# PROC091F_HD_CONN_PWR_SW.net
KiCad netlist of a schematic drawn in Altium Designer
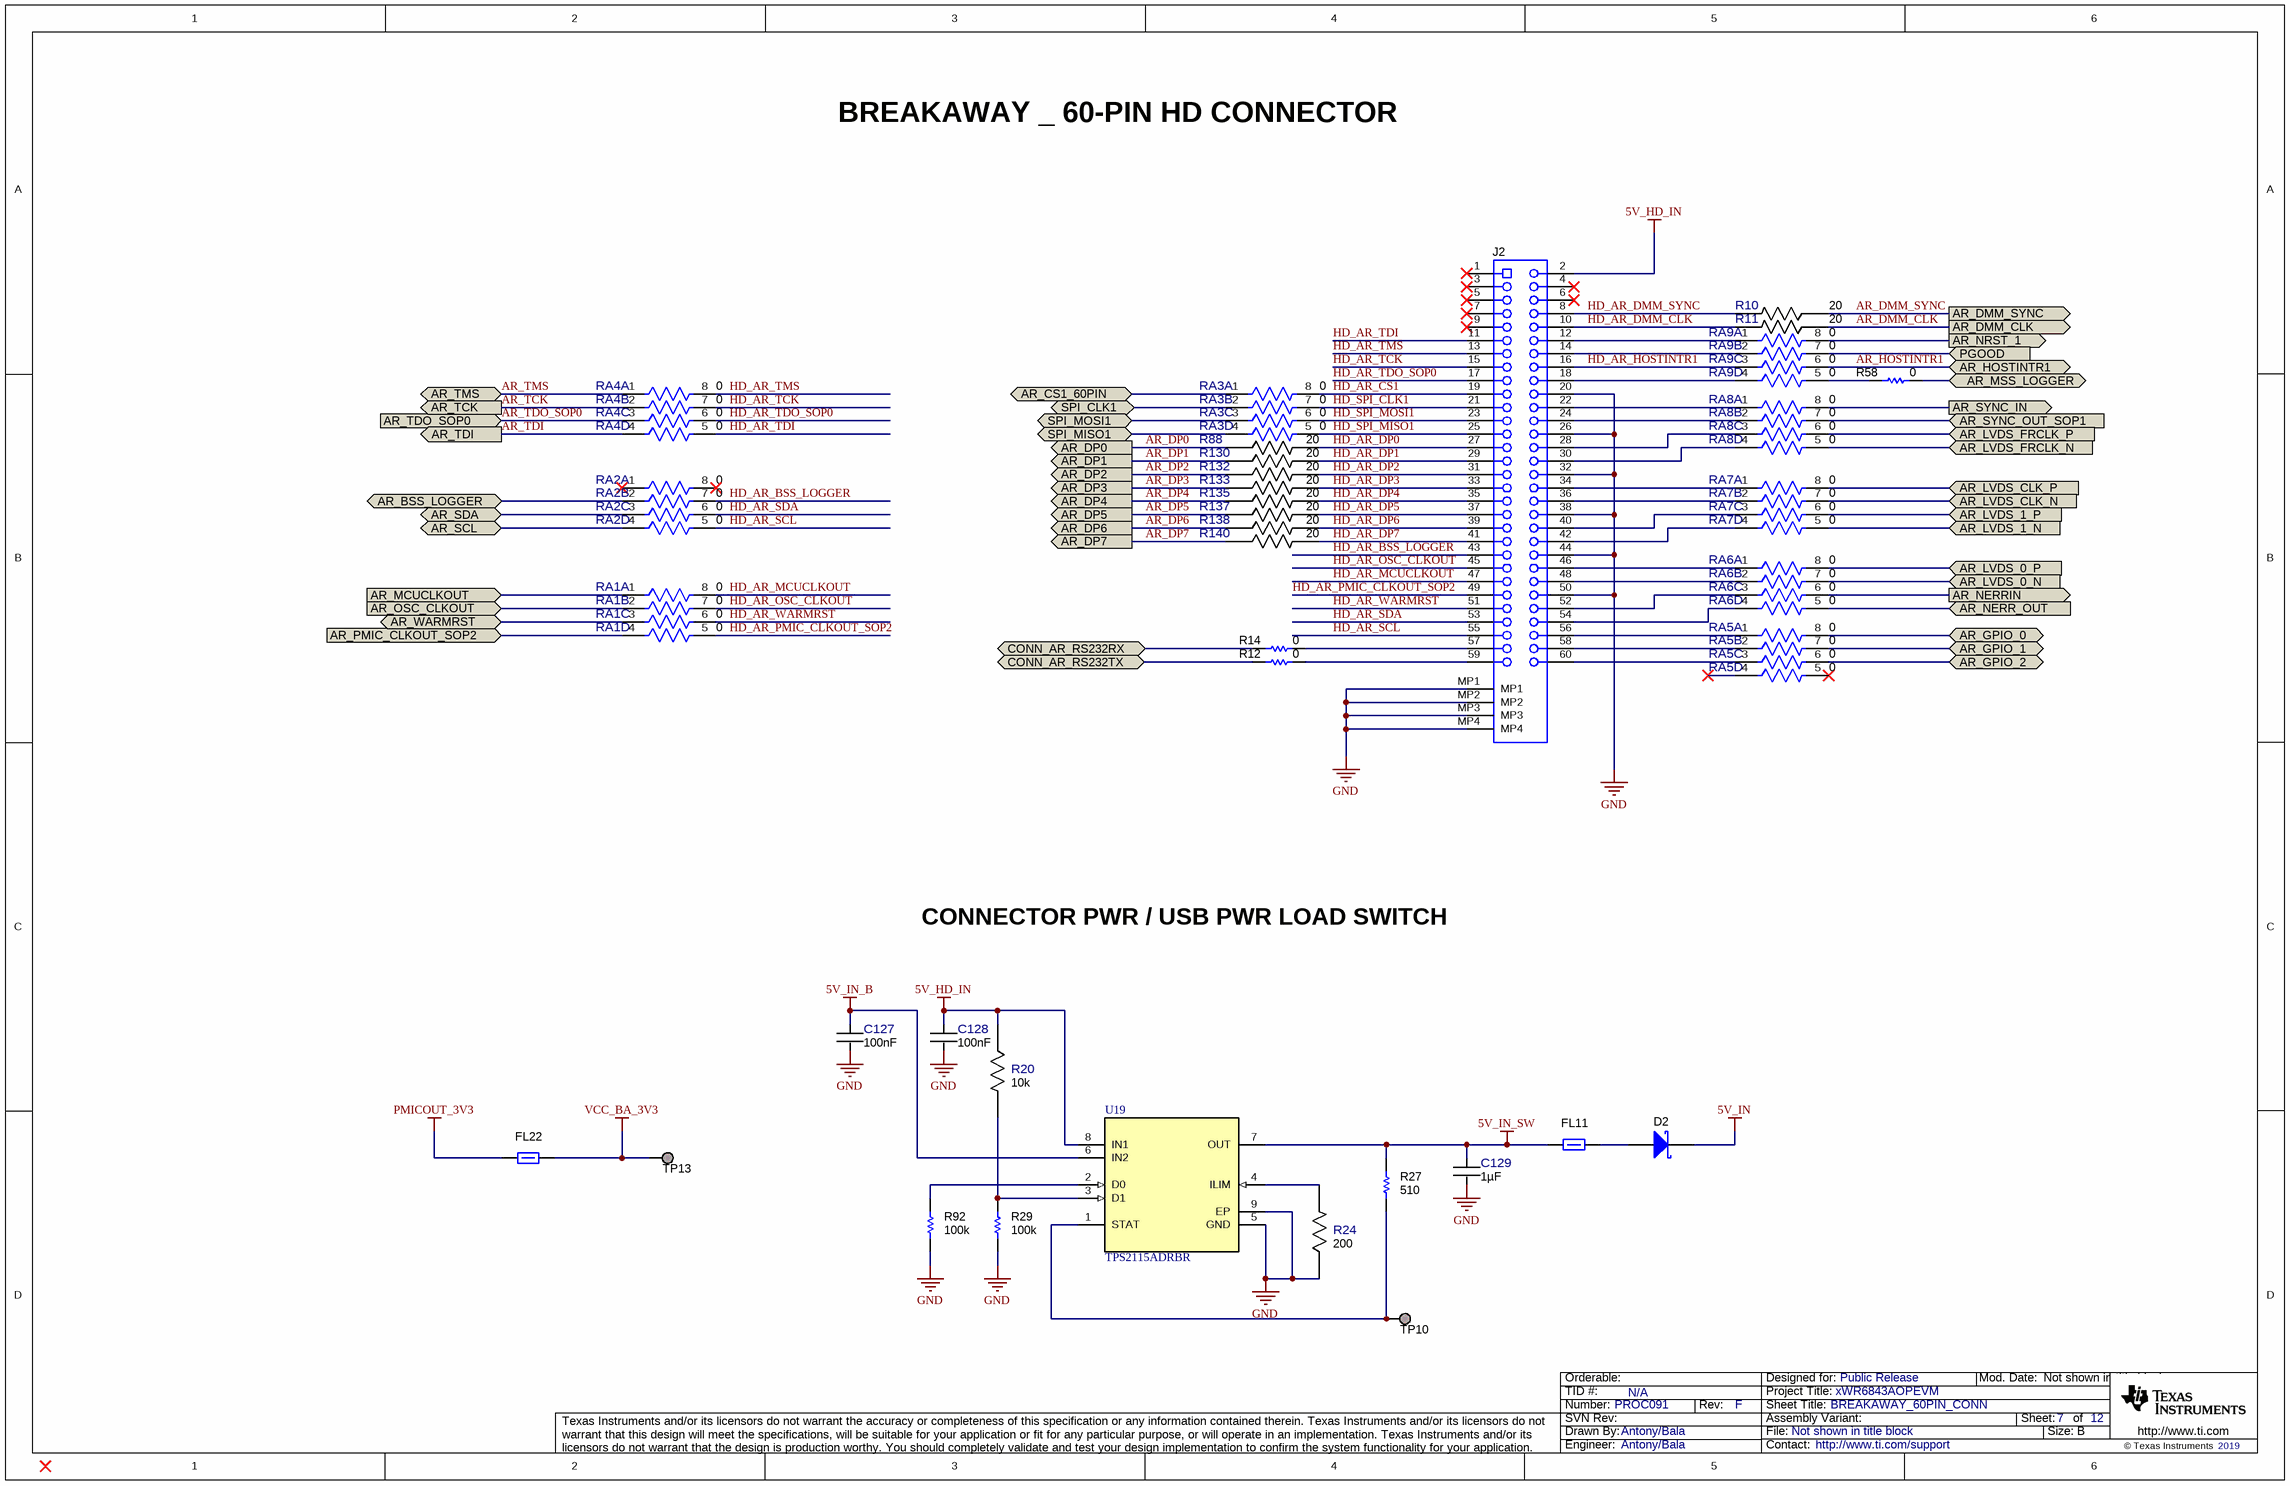
[diagram p0: PROC091F_HD_CONN_PWR_SW.SchDoc]

(export (version "E")
  (design (tool "Eeschema 10.0.6"))
  (components
    (comp (ref "C127")
      (value "GRM033R6YA104KE14D")
      (footprint "FP-GRM033R6YA104KE14D_0201 (0603 Metric)-IPC_C")
      (description "Cap Ceramic 0.1uF 35V X5R 10% Pad SMD 0201 85C T/R")
      (fields (field (name "CAP_F") "100nF") (field (name "MANUFACTURER") "Murata Electronics North America"))
      (libsource (lib "Altium Vault - TI") (part "SYM-B32642B0223J"))
    )
    (comp (ref "C128")
      (value "GRM033R6YA104KE14D")
      (footprint "FP-GRM033R6YA104KE14D_0201 (0603 Metric)-IPC_C")
      (description "Cap Ceramic 0.1uF 35V X5R 10% Pad SMD 0201 85C T/R")
      (fields (field (name "CAP_F") "100nF") (field (name "MANUFACTURER") "Murata Electronics North America"))
      (libsource (lib "Altium Vault - TI") (part "SYM-B32642B0223J"))
    )
    (comp (ref "C129")
      (value "CL03A105MO3NRNH")
      (footprint "FP-CL03A105MO3NRNH_0201-IPC_C")
      (description "1µF ±20% 16V Ceramic Capacitor X5R 0201")
      (fields (field (name "CAP_F") "1µF") (field (name "MANUFACTURER") "Samsung Electro-Mechanics"))
      (libsource (lib "Altium Vault - TI") (part "SYM-B32642B0223J"))
    )
    (comp (ref "D2")
      (value "NSR20F30NXT5G")
      (footprint "DSN2_0603")
      (description "Diode, Schottky, 30 V, 2 A, 2-XFDFN")
      (fields (field (name "MANUFACTURER") "ON Semiconductor"))
      (libsource (lib "Altium Vault - TI") (part "DIODE_SCHOTTKY"))
    )
    (comp (ref "FL11")
      (value "BLM15PD300SZ1D")
      (footprint "0402L")
      (description "Inductor, Ferrite Bead, Ferrite, 2.2 A, 0.035 ohm, AEC-Q200 Grade 1, SMD")
      (fields (field (name "MANUFACTURER") "MuRata") (field (name "PUBLISHER") "Texas Instruments"))
      (libsource (lib "Altium Vault - TI") (part "Ferrite_Bead"))
    )
    (comp (ref "FL22")
      (value "BLM15PD300SZ1D")
      (footprint "0402L")
      (description "Inductor, Ferrite Bead, Ferrite, 2.2 A, 0.035 ohm, AEC-Q200 Grade 1, SMD")
      (fields (field (name "MANUFACTURER") "MuRata") (field (name "PUBLISHER") "Texas Instruments"))
      (libsource (lib "Altium Vault - TI") (part "Ferrite_Bead"))
    )
    (comp (ref "J2")
      (value "QSH-030-01-L-D-A")
      (footprint "Samtec_QSH-030-01-X-D-A")
      (description "Receptacle, 0.5 mm, 30x2, Gold, TH")
      (fields (field (name "MANUFACTURER") "Samtec") (field (name "PUBLISHER") "Texas Instruments"))
      (libsource (lib "Altium Vault - TI") (part "Receptacle_30x2_4MP_LeftRight"))
    )
    (comp (ref "R10")
      (value "AC0201FR-0720RL")
      (footprint "FP-AC0201FR-0720RL_0201-IPC_C")
      (description "RES SMD 20 OHM 1% 1/20W 0201")
      (fields (field (name "MANUFACTURER") "Yageo") (field (name "RES_OHM") "20"))
      (libsource (lib "Altium Vault - TI") (part "SYM-PMR18EZPJ000"))
    )
    (comp (ref "R11")
      (value "AC0201FR-0720RL")
      (footprint "FP-AC0201FR-0720RL_0201-IPC_C")
      (description "RES SMD 20 OHM 1% 1/20W 0201")
      (fields (field (name "MANUFACTURER") "Yageo") (field (name "RES_OHM") "20"))
      (libsource (lib "Altium Vault - TI") (part "SYM-PMR18EZPJ000"))
    )
    (comp (ref "R12")
      (value "RC0201JR-070RL")
      (footprint "FP-RC0201JR-070RL_0201 (0603 Metric)-MFG")
      (description "RES SMD 0 OHM JUMPER 1/20W 0201")
      (fields (field (name "MANUFACTURER") "Yageo") (field (name "RES_OHM") "0"))
      (libsource (lib "Altium Vault - TI") (part "SYM-WSR3R1500F"))
    )
    (comp (ref "R14")
      (value "RC0201JR-070RL")
      (footprint "FP-RC0201JR-070RL_0201 (0603 Metric)-MFG")
      (description "RES SMD 0 OHM JUMPER 1/20W 0201")
      (fields (field (name "MANUFACTURER") "Yageo") (field (name "RES_OHM") "0"))
      (libsource (lib "Altium Vault - TI") (part "SYM-WSR3R1500F"))
    )
    (comp (ref "R20")
      (value "RR0306P-103-D")
      (footprint "FP-RR0306P-103-D_0201-IPC_C")
      (description "10 kOhms ±0.5% 0.05W, 1/20W Chip Resistor 0201 (0603 Metric)  Thin Film")
      (fields (field (name "MANUFACTURER") "Susumu") (field (name "RES_OHM") "10k"))
      (libsource (lib "Altium Vault - TI") (part "SYM-PMR18EZPJ000"))
    )
    (comp (ref "R24")
      (value "CRCW0402200RFKEDHP")
      (footprint "FP-CRCW0402200RFKEDHP_0402-IPC_C")
      (description "RES SMD 200 OHM 1% 1/5W 0402")
      (fields (field (name "MANUFACTURER") "Vishay Dale") (field (name "RES_OHM") "200"))
      (libsource (lib "Altium Vault - TI") (part "SYM-PMR18EZPJ000"))
    )
    (comp (ref "R27")
      (value "510")
      (footprint "0201L")
      (description "RES, 510, 5%, 0.05 W, 0201")
      (fields
        (field (name "MANUFACTURER") "Yageo America")
        (field (name "PARTNUMBER") "RC0201JR-07510RL")
        (field (name "PUBLISHER") "Texas Instruments")
      )
      (libsource (lib "Altium Vault - TI") (part "Resistor"))
    )
    (comp (ref "R29")
      (value "100k")
      (footprint "0201L")
      (description "RES, 100 k, 1%, 0.05 W, 0201")
      (fields (field (name "MANUFACTURER") "Vishay-Dale") (field (name "PARTNUMBER") "CRCW0201100KFKED"))
      (libsource (lib "Altium Vault - TI") (part "Resistor"))
    )
    (comp (ref "R58")
      (value "RC0201JR-070RL")
      (footprint "FP-RC0201JR-070RL_0201 (0603 Metric)-MFG")
      (description "RES SMD 0 OHM JUMPER 1/20W 0201")
      (fields (field (name "MANUFACTURER") "Yageo") (field (name "RES_OHM") "0"))
      (libsource (lib "Altium Vault - TI") (part "SYM-WSR3R1500F"))
    )
    (comp (ref "R88")
      (value "AC0201FR-0720RL")
      (footprint "FP-AC0201FR-0720RL_0201-IPC_C")
      (description "RES SMD 20 OHM 1% 1/20W 0201")
      (fields (field (name "MANUFACTURER") "Yageo") (field (name "RES_OHM") "20"))
      (libsource (lib "Altium Vault - TI") (part "SYM-PMR18EZPJ000"))
    )
    (comp (ref "R92")
      (value "100k")
      (footprint "0201L")
      (description "RES, 100 k, 1%, 0.05 W, 0201")
      (fields (field (name "MANUFACTURER") "Vishay-Dale") (field (name "PARTNUMBER") "CRCW0201100KFKED"))
      (libsource (lib "Altium Vault - TI") (part "Resistor"))
    )
    (comp (ref "R130")
      (value "AC0201FR-0720RL")
      (footprint "FP-AC0201FR-0720RL_0201-IPC_C")
      (description "RES SMD 20 OHM 1% 1/20W 0201")
      (fields (field (name "MANUFACTURER") "Yageo") (field (name "RES_OHM") "20"))
      (libsource (lib "Altium Vault - TI") (part "SYM-PMR18EZPJ000"))
    )
    (comp (ref "R132")
      (value "AC0201FR-0720RL")
      (footprint "FP-AC0201FR-0720RL_0201-IPC_C")
      (description "RES SMD 20 OHM 1% 1/20W 0201")
      (fields (field (name "MANUFACTURER") "Yageo") (field (name "RES_OHM") "20"))
      (libsource (lib "Altium Vault - TI") (part "SYM-PMR18EZPJ000"))
    )
    (comp (ref "R133")
      (value "AC0201FR-0720RL")
      (footprint "FP-AC0201FR-0720RL_0201-IPC_C")
      (description "RES SMD 20 OHM 1% 1/20W 0201")
      (fields (field (name "MANUFACTURER") "Yageo") (field (name "RES_OHM") "20"))
      (libsource (lib "Altium Vault - TI") (part "SYM-PMR18EZPJ000"))
    )
    (comp (ref "R135")
      (value "AC0201FR-0720RL")
      (footprint "FP-AC0201FR-0720RL_0201-IPC_C")
      (description "RES SMD 20 OHM 1% 1/20W 0201")
      (fields (field (name "MANUFACTURER") "Yageo") (field (name "RES_OHM") "20"))
      (libsource (lib "Altium Vault - TI") (part "SYM-PMR18EZPJ000"))
    )
    (comp (ref "R137")
      (value "AC0201FR-0720RL")
      (footprint "FP-AC0201FR-0720RL_0201-IPC_C")
      (description "RES SMD 20 OHM 1% 1/20W 0201")
      (fields (field (name "MANUFACTURER") "Yageo") (field (name "RES_OHM") "20"))
      (libsource (lib "Altium Vault - TI") (part "SYM-PMR18EZPJ000"))
    )
    (comp (ref "R138")
      (value "AC0201FR-0720RL")
      (footprint "FP-AC0201FR-0720RL_0201-IPC_C")
      (description "RES SMD 20 OHM 1% 1/20W 0201")
      (fields (field (name "MANUFACTURER") "Yageo") (field (name "RES_OHM") "20"))
      (libsource (lib "Altium Vault - TI") (part "SYM-PMR18EZPJ000"))
    )
    (comp (ref "R140")
      (value "AC0201FR-0720RL")
      (footprint "FP-AC0201FR-0720RL_0201-IPC_C")
      (description "RES SMD 20 OHM 1% 1/20W 0201")
      (fields (field (name "MANUFACTURER") "Yageo") (field (name "RES_OHM") "20"))
      (libsource (lib "Altium Vault - TI") (part "SYM-PMR18EZPJ000"))
    )
    (comp (ref "RA1")
      (value "EXB-18VR000X")
      (footprint "FP-EXB-18VR000X_0502-MFG")
      (description "RES ARRAY 4 RES ZERO OHM 0502")
      (fields (field (name "MANUFACTURER") "Panasonic Electronic Components") (field (name "RES_OHM") "0"))
      (libsource (lib "Altium Vault - TI") (part "SYM-EXB-18VR000X"))
    )
    (comp (ref "RA2")
      (value "EXB-18VR000X")
      (footprint "FP-EXB-18VR000X_0502-MFG")
      (description "RES ARRAY 4 RES ZERO OHM 0502")
      (fields (field (name "MANUFACTURER") "Panasonic Electronic Components") (field (name "RES_OHM") "0"))
      (libsource (lib "Altium Vault - TI") (part "SYM-EXB-18VR000X"))
    )
    (comp (ref "RA3")
      (value "EXB-18VR000X")
      (footprint "FP-EXB-18VR000X_0502-MFG")
      (description "RES ARRAY 4 RES ZERO OHM 0502")
      (fields (field (name "MANUFACTURER") "Panasonic Electronic Components") (field (name "RES_OHM") "0"))
      (libsource (lib "Altium Vault - TI") (part "SYM-EXB-18VR000X"))
    )
    (comp (ref "RA4")
      (value "EXB-18VR000X")
      (footprint "FP-EXB-18VR000X_0502-MFG")
      (description "RES ARRAY 4 RES ZERO OHM 0502")
      (fields (field (name "MANUFACTURER") "Panasonic Electronic Components") (field (name "RES_OHM") "0"))
      (libsource (lib "Altium Vault - TI") (part "SYM-EXB-18VR000X"))
    )
    (comp (ref "RA5")
      (value "EXB-18VR000X")
      (footprint "FP-EXB-18VR000X_0502-MFG")
      (description "RES ARRAY 4 RES ZERO OHM 0502")
      (fields (field (name "MANUFACTURER") "Panasonic Electronic Components") (field (name "RES_OHM") "0"))
      (libsource (lib "Altium Vault - TI") (part "SYM-EXB-18VR000X"))
    )
    (comp (ref "RA6")
      (value "EXB-18VR000X")
      (footprint "FP-EXB-18VR000X_0502-MFG")
      (description "RES ARRAY 4 RES ZERO OHM 0502")
      (fields (field (name "MANUFACTURER") "Panasonic Electronic Components") (field (name "RES_OHM") "0"))
      (libsource (lib "Altium Vault - TI") (part "SYM-EXB-18VR000X"))
    )
    (comp (ref "RA7")
      (value "EXB-18VR000X")
      (footprint "FP-EXB-18VR000X_0502-MFG")
      (description "RES ARRAY 4 RES ZERO OHM 0502")
      (fields (field (name "MANUFACTURER") "Panasonic Electronic Components") (field (name "RES_OHM") "0"))
      (libsource (lib "Altium Vault - TI") (part "SYM-EXB-18VR000X"))
    )
    (comp (ref "RA8")
      (value "EXB-18VR000X")
      (footprint "FP-EXB-18VR000X_0502-MFG")
      (description "RES ARRAY 4 RES ZERO OHM 0502")
      (fields (field (name "MANUFACTURER") "Panasonic Electronic Components") (field (name "RES_OHM") "0"))
      (libsource (lib "Altium Vault - TI") (part "SYM-EXB-18VR000X"))
    )
    (comp (ref "RA9")
      (value "EXB-18VR000X")
      (footprint "FP-EXB-18VR000X_0502-MFG")
      (description "RES ARRAY 4 RES ZERO OHM 0502")
      (fields (field (name "MANUFACTURER") "Panasonic Electronic Components") (field (name "RES_OHM") "0"))
      (libsource (lib "Altium Vault - TI") (part "SYM-EXB-18VR000X"))
    )
    (comp (ref "TP10")
      (value "TESTPOINT")
      (footprint "TP_25MIL-SMT")
      (description "TEST POINT.  No entry in BOM.")
      (libsource (lib "Altium Vault - TI") (part "TESTPOINT"))
    )
    (comp (ref "TP13")
      (value "TESTPOINT")
      (footprint "TP_25MIL-SMT")
      (description "TEST POINT.  No entry in BOM.")
      (libsource (lib "Altium Vault - TI") (part "TESTPOINT"))
    )
    (comp (ref "U19")
      (value "TPS2115ADRBR")
      (footprint "DRB0008B")
      (fields (field (name "MANUFACTURER") "Texas Instruments"))
      (libsource (lib "Altium Vault - TI") (part "TI-TPS2115ADRB8-2400X1650TP"))
    )
  )
  (nets
    (net (code "1") (name "/AR_BSS_LOGGER") (class "Default")
      (node (ref "RA2") (pin "2") (pinfunction "2_2") (pintype "passive"))
    )
    (net (code "2") (name "/AR_CS1_60PIN") (class "Default")
      (node (ref "RA3") (pin "1") (pinfunction "1_1") (pintype "passive"))
    )
    (net (code "3") (name "/AR_DMM_CLK") (class "Default")
      (node (ref "R11") (pin "1") (pinfunction "1_1") (pintype "passive"))
    )
    (net (code "4") (name "/AR_DMM_SYNC") (class "Default")
      (node (ref "R10") (pin "1") (pinfunction "1_1") (pintype "passive"))
    )
    (net (code "5") (name "/AR_DP0") (class "Default")
      (node (ref "R88") (pin "1") (pinfunction "1_1") (pintype "passive"))
    )
    (net (code "6") (name "/AR_DP1") (class "Default")
      (node (ref "R130") (pin "1") (pinfunction "1_1") (pintype "passive"))
    )
    (net (code "7") (name "/AR_DP2") (class "Default")
      (node (ref "R132") (pin "1") (pinfunction "1_1") (pintype "passive"))
    )
    (net (code "8") (name "/AR_DP3") (class "Default")
      (node (ref "R133") (pin "1") (pinfunction "1_1") (pintype "passive"))
    )
    (net (code "9") (name "/AR_DP4") (class "Default")
      (node (ref "R135") (pin "1") (pinfunction "1_1") (pintype "passive"))
    )
    (net (code "10") (name "/AR_DP5") (class "Default")
      (node (ref "R137") (pin "1") (pinfunction "1_1") (pintype "passive"))
    )
    (net (code "11") (name "/AR_DP6") (class "Default")
      (node (ref "R138") (pin "1") (pinfunction "1_1") (pintype "passive"))
    )
    (net (code "12") (name "/AR_DP7") (class "Default")
      (node (ref "R140") (pin "1") (pinfunction "1_1") (pintype "passive"))
    )
    (net (code "13") (name "/AR_GPIO_0") (class "Default")
      (node (ref "RA5") (pin "8") (pinfunction "8_8") (pintype "passive"))
    )
    (net (code "14") (name "/AR_GPIO_1") (class "Default")
      (node (ref "RA5") (pin "7") (pinfunction "7_7") (pintype "passive"))
    )
    (net (code "15") (name "/AR_GPIO_2") (class "Default")
      (node (ref "RA5") (pin "6") (pinfunction "6_6") (pintype "passive"))
    )
    (net (code "16") (name "/AR_HOSTINTR1") (class "Default")
      (node (ref "RA9") (pin "6") (pinfunction "6_6") (pintype "passive"))
    )
    (net (code "17") (name "/AR_LVDS_0_N") (class "Default")
      (node (ref "RA6") (pin "7") (pinfunction "7_7") (pintype "passive"))
    )
    (net (code "18") (name "/AR_LVDS_0_P") (class "Default")
      (node (ref "RA6") (pin "8") (pinfunction "8_8") (pintype "passive"))
    )
    (net (code "19") (name "/AR_LVDS_1_N") (class "Default")
      (node (ref "RA7") (pin "5") (pinfunction "5_5") (pintype "passive"))
    )
    (net (code "20") (name "/AR_LVDS_1_P") (class "Default")
      (node (ref "RA7") (pin "6") (pinfunction "6_6") (pintype "passive"))
    )
    (net (code "21") (name "/AR_LVDS_CLK_N") (class "Default")
      (node (ref "RA7") (pin "7") (pinfunction "7_7") (pintype "passive"))
    )
    (net (code "22") (name "/AR_LVDS_CLK_P") (class "Default")
      (node (ref "RA7") (pin "8") (pinfunction "8_8") (pintype "passive"))
    )
    (net (code "23") (name "/AR_LVDS_FRCLK_N") (class "Default")
      (node (ref "RA8") (pin "5") (pinfunction "5_5") (pintype "passive"))
    )
    (net (code "24") (name "/AR_LVDS_FRCLK_P") (class "Default")
      (node (ref "RA8") (pin "6") (pinfunction "6_6") (pintype "passive"))
    )
    (net (code "25") (name "/AR_MCUCLKOUT") (class "Default")
      (node (ref "RA1") (pin "1") (pinfunction "1_1") (pintype "passive"))
    )
    (net (code "26") (name "/AR_MSS_LOGGER") (class "Default")
      (node (ref "R58") (pin "1") (pinfunction "1_1") (pintype "passive"))
    )
    (net (code "27") (name "/AR_NERRIN") (class "Default")
      (node (ref "RA6") (pin "6") (pinfunction "6_6") (pintype "passive"))
    )
    (net (code "28") (name "/AR_NERR_OUT") (class "Default")
      (node (ref "RA6") (pin "5") (pinfunction "5_5") (pintype "passive"))
    )
    (net (code "29") (name "/AR_NRST_1") (class "Default")
      (node (ref "RA9") (pin "8") (pinfunction "8_8") (pintype "passive"))
    )
    (net (code "30") (name "/AR_OSC_CLKOUT") (class "Default")
      (node (ref "RA1") (pin "2") (pinfunction "2_2") (pintype "passive"))
    )
    (net (code "31") (name "/AR_PMIC_CLKOUT_SOP2") (class "Default")
      (node (ref "RA1") (pin "4") (pinfunction "4_4") (pintype "passive"))
    )
    (net (code "32") (name "/AR_SCL") (class "Default")
      (node (ref "RA2") (pin "4") (pinfunction "4_4") (pintype "passive"))
    )
    (net (code "33") (name "/AR_SDA") (class "Default")
      (node (ref "RA2") (pin "3") (pinfunction "3_3") (pintype "passive"))
    )
    (net (code "34") (name "/AR_SYNC_IN") (class "Default")
      (node (ref "RA8") (pin "8") (pinfunction "8_8") (pintype "passive"))
    )
    (net (code "35") (name "/AR_SYNC_OUT_SOP1") (class "Default")
      (node (ref "RA8") (pin "7") (pinfunction "7_7") (pintype "passive"))
    )
    (net (code "36") (name "/AR_TCK") (class "Default")
      (node (ref "RA4") (pin "2") (pinfunction "2_2") (pintype "passive"))
    )
    (net (code "37") (name "/AR_TDI") (class "Default")
      (node (ref "RA4") (pin "4") (pinfunction "4_4") (pintype "passive"))
    )
    (net (code "38") (name "/AR_TDO_SOP0") (class "Default")
      (node (ref "RA4") (pin "3") (pinfunction "3_3") (pintype "passive"))
    )
    (net (code "39") (name "/AR_TMS") (class "Default")
      (node (ref "RA4") (pin "1") (pinfunction "1_1") (pintype "passive"))
    )
    (net (code "40") (name "/AR_WARMRST") (class "Default")
      (node (ref "RA1") (pin "3") (pinfunction "3_3") (pintype "passive"))
    )
    (net (code "41") (name "/CONN_AR_RS232RX") (class "Default")
      (node (ref "R14") (pin "2") (pinfunction "2_2") (pintype "passive"))
    )
    (net (code "42") (name "/CONN_AR_RS232TX") (class "Default")
      (node (ref "R12") (pin "2") (pinfunction "2_2") (pintype "passive"))
    )
    (net (code "43") (name "/HD_AR_BSS_LOGGER") (class "Default")
      (node (ref "J2") (pin "43") (pinfunction "43_43") (pintype "passive"))
      (node (ref "RA2") (pin "7") (pinfunction "7_7") (pintype "passive"))
    )
    (net (code "44") (name "/HD_AR_CS1") (class "Default")
      (node (ref "J2") (pin "19") (pinfunction "19_19") (pintype "passive"))
      (node (ref "RA3") (pin "8") (pinfunction "8_8") (pintype "passive"))
    )
    (net (code "45") (name "/HD_AR_DMM_CLK") (class "Default")
      (node (ref "J2") (pin "10") (pinfunction "10_10") (pintype "passive"))
      (node (ref "R11") (pin "2") (pinfunction "2_2") (pintype "passive"))
    )
    (net (code "46") (name "/HD_AR_DMM_SYNC") (class "Default")
      (node (ref "J2") (pin "8") (pinfunction "8_8") (pintype "passive"))
      (node (ref "R10") (pin "2") (pinfunction "2_2") (pintype "passive"))
    )
    (net (code "47") (name "/HD_AR_DP0") (class "Default")
      (node (ref "J2") (pin "27") (pinfunction "27_27") (pintype "passive"))
      (node (ref "R88") (pin "2") (pinfunction "2_2") (pintype "passive"))
    )
    (net (code "48") (name "/HD_AR_DP1") (class "Default")
      (node (ref "J2") (pin "29") (pinfunction "29_29") (pintype "passive"))
      (node (ref "R130") (pin "2") (pinfunction "2_2") (pintype "passive"))
    )
    (net (code "49") (name "/HD_AR_DP2") (class "Default")
      (node (ref "J2") (pin "31") (pinfunction "31_31") (pintype "passive"))
      (node (ref "R132") (pin "2") (pinfunction "2_2") (pintype "passive"))
    )
    (net (code "50") (name "/HD_AR_DP3") (class "Default")
      (node (ref "J2") (pin "33") (pinfunction "33_33") (pintype "passive"))
      (node (ref "R133") (pin "2") (pinfunction "2_2") (pintype "passive"))
    )
    (net (code "51") (name "/HD_AR_DP4") (class "Default")
      (node (ref "J2") (pin "35") (pinfunction "35_35") (pintype "passive"))
      (node (ref "R135") (pin "2") (pinfunction "2_2") (pintype "passive"))
    )
    (net (code "52") (name "/HD_AR_DP5") (class "Default")
      (node (ref "J2") (pin "37") (pinfunction "37_37") (pintype "passive"))
      (node (ref "R137") (pin "2") (pinfunction "2_2") (pintype "passive"))
    )
    (net (code "53") (name "/HD_AR_DP6") (class "Default")
      (node (ref "J2") (pin "39") (pinfunction "39_39") (pintype "passive"))
      (node (ref "R138") (pin "2") (pinfunction "2_2") (pintype "passive"))
    )
    (net (code "54") (name "/HD_AR_DP7") (class "Default")
      (node (ref "J2") (pin "41") (pinfunction "41_41") (pintype "passive"))
      (node (ref "R140") (pin "2") (pinfunction "2_2") (pintype "passive"))
    )
    (net (code "55") (name "/HD_AR_HOSTINTR1") (class "Default")
      (node (ref "J2") (pin "16") (pinfunction "16_16") (pintype "passive"))
      (node (ref "RA9") (pin "3") (pinfunction "3_3") (pintype "passive"))
    )
    (net (code "56") (name "/HD_AR_MCUCLKOUT") (class "Default")
      (node (ref "J2") (pin "47") (pinfunction "47_47") (pintype "passive"))
      (node (ref "RA1") (pin "8") (pinfunction "8_8") (pintype "passive"))
    )
    (net (code "57") (name "/HD_AR_OSC_CLKOUT") (class "Default")
      (node (ref "J2") (pin "45") (pinfunction "45_45") (pintype "passive"))
      (node (ref "RA1") (pin "7") (pinfunction "7_7") (pintype "passive"))
    )
    (net (code "58") (name "/HD_AR_PMIC_CLKOUT_SOP2") (class "Default")
      (node (ref "J2") (pin "49") (pinfunction "49_49") (pintype "passive"))
      (node (ref "RA1") (pin "5") (pinfunction "5_5") (pintype "passive"))
    )
    (net (code "59") (name "/HD_AR_SCL") (class "Default")
      (node (ref "J2") (pin "55") (pinfunction "55_55") (pintype "passive"))
      (node (ref "RA2") (pin "5") (pinfunction "5_5") (pintype "passive"))
    )
    (net (code "60") (name "/HD_AR_SDA") (class "Default")
      (node (ref "J2") (pin "53") (pinfunction "53_53") (pintype "passive"))
      (node (ref "RA2") (pin "6") (pinfunction "6_6") (pintype "passive"))
    )
    (net (code "61") (name "/HD_AR_TCK") (class "Default")
      (node (ref "J2") (pin "15") (pinfunction "15_15") (pintype "passive"))
      (node (ref "RA4") (pin "7") (pinfunction "7_7") (pintype "passive"))
    )
    (net (code "62") (name "/HD_AR_TDI") (class "Default")
      (node (ref "J2") (pin "11") (pinfunction "11_11") (pintype "passive"))
      (node (ref "RA4") (pin "5") (pinfunction "5_5") (pintype "passive"))
    )
    (net (code "63") (name "/HD_AR_TDO_SOP0") (class "Default")
      (node (ref "J2") (pin "17") (pinfunction "17_17") (pintype "passive"))
      (node (ref "RA4") (pin "6") (pinfunction "6_6") (pintype "passive"))
    )
    (net (code "64") (name "/HD_AR_TMS") (class "Default")
      (node (ref "J2") (pin "13") (pinfunction "13_13") (pintype "passive"))
      (node (ref "RA4") (pin "8") (pinfunction "8_8") (pintype "passive"))
    )
    (net (code "65") (name "/HD_AR_WARMRST") (class "Default")
      (node (ref "J2") (pin "51") (pinfunction "51_51") (pintype "passive"))
      (node (ref "RA1") (pin "6") (pinfunction "6_6") (pintype "passive"))
    )
    (net (code "66") (name "/HD_SPI_CLK1") (class "Default")
      (node (ref "J2") (pin "21") (pinfunction "21_21") (pintype "passive"))
      (node (ref "RA3") (pin "7") (pinfunction "7_7") (pintype "passive"))
    )
    (net (code "67") (name "/HD_SPI_MISO1") (class "Default")
      (node (ref "J2") (pin "25") (pinfunction "25_25") (pintype "passive"))
      (node (ref "RA3") (pin "5") (pinfunction "5_5") (pintype "passive"))
    )
    (net (code "68") (name "/HD_SPI_MOSI1") (class "Default")
      (node (ref "J2") (pin "23") (pinfunction "23_23") (pintype "passive"))
      (node (ref "RA3") (pin "6") (pinfunction "6_6") (pintype "passive"))
    )
    (net (code "69") (name "/PGOOD") (class "Default")
      (node (ref "RA9") (pin "7") (pinfunction "7_7") (pintype "passive"))
    )
    (net (code "70") (name "/SPI_CLK1") (class "Default")
      (node (ref "RA3") (pin "2") (pinfunction "2_2") (pintype "passive"))
    )
    (net (code "71") (name "/SPI_MISO1") (class "Default")
      (node (ref "RA3") (pin "4") (pinfunction "4_4") (pintype "passive"))
    )
    (net (code "72") (name "/SPI_MOSI1") (class "Default")
      (node (ref "RA3") (pin "3") (pinfunction "3_3") (pintype "passive"))
    )
    (net (code "73") (name "5V_HD_IN") (class "Default")
      (node (ref "C128") (pin "1") (pinfunction "1_1") (pintype "passive"))
      (node (ref "J2") (pin "2") (pinfunction "2_2") (pintype "passive"))
      (node (ref "R20") (pin "1") (pinfunction "1_1") (pintype "passive"))
      (node (ref "U19") (pin "8") (pinfunction "IN1_8") (pintype "power_in"))
    )
    (net (code "74") (name "5V_IN") (class "Default")
      (node (ref "D2") (pin "1") (pinfunction "K_1") (pintype "passive"))
    )
    (net (code "75") (name "5V_IN_B") (class "Default")
      (node (ref "C127") (pin "1") (pinfunction "1_1") (pintype "passive"))
      (node (ref "U19") (pin "6") (pinfunction "IN2_6") (pintype "power_in"))
    )
    (net (code "76") (name "5V_IN_SW") (class "Default")
      (node (ref "C129") (pin "1") (pinfunction "1_1") (pintype "passive"))
      (node (ref "FL11") (pin "1") (pinfunction "1_1") (pintype "passive"))
      (node (ref "R27") (pin "1") (pinfunction "1_1") (pintype "passive"))
      (node (ref "U19") (pin "7") (pinfunction "OUT_7") (pintype "power_in"))
    )
    (net (code "77") (name "GND") (class "Default")
      (node (ref "C127") (pin "2") (pinfunction "2_2") (pintype "passive"))
      (node (ref "C128") (pin "2") (pinfunction "2_2") (pintype "passive"))
      (node (ref "C129") (pin "2") (pinfunction "2_2") (pintype "passive"))
      (node (ref "J2") (pin "20") (pinfunction "20_20") (pintype "passive"))
      (node (ref "J2") (pin "26") (pinfunction "26_26") (pintype "passive"))
      (node (ref "J2") (pin "32") (pinfunction "32_32") (pintype "passive"))
      (node (ref "J2") (pin "38") (pinfunction "38_38") (pintype "passive"))
      (node (ref "J2") (pin "44") (pinfunction "44_44") (pintype "passive"))
      (node (ref "J2") (pin "50") (pinfunction "50_50") (pintype "passive"))
      (node (ref "J2") (pin "MP1") (pinfunction "MP1_MP1") (pintype "passive"))
      (node (ref "J2") (pin "MP2") (pinfunction "MP2_MP2") (pintype "passive"))
      (node (ref "J2") (pin "MP3") (pinfunction "MP3_MP3") (pintype "passive"))
      (node (ref "J2") (pin "MP4") (pinfunction "MP4_MP4") (pintype "passive"))
      (node (ref "R24") (pin "1") (pinfunction "1_1") (pintype "passive"))
      (node (ref "R29") (pin "1") (pinfunction "1_1") (pintype "passive"))
      (node (ref "R92") (pin "2") (pinfunction "2_2") (pintype "passive"))
      (node (ref "U19") (pin "5") (pinfunction "GND_5") (pintype "power_in"))
      (node (ref "U19") (pin "9") (pinfunction "EP_9") (pintype "power_in"))
    )
    (net (code "78") (name "Net-(D2-A)") (class "Default")
      (node (ref "D2") (pin "2") (pinfunction "A_2") (pintype "passive"))
      (node (ref "FL11") (pin "2") (pinfunction "2_2") (pintype "passive"))
    )
    (net (code "79") (name "Net-(J2-Pad12)") (class "Default")
      (node (ref "J2") (pin "12") (pinfunction "12_12") (pintype "passive"))
      (node (ref "RA9") (pin "1") (pinfunction "1_1") (pintype "passive"))
    )
    (net (code "80") (name "Net-(J2-Pad14)") (class "Default")
      (node (ref "J2") (pin "14") (pinfunction "14_14") (pintype "passive"))
      (node (ref "RA9") (pin "2") (pinfunction "2_2") (pintype "passive"))
    )
    (net (code "81") (name "Net-(J2-Pad18)") (class "Default")
      (node (ref "J2") (pin "18") (pinfunction "18_18") (pintype "passive"))
      (node (ref "RA9") (pin "4") (pinfunction "4_4") (pintype "passive"))
    )
    (net (code "82") (name "Net-(J2-Pad22)") (class "Default")
      (node (ref "J2") (pin "22") (pinfunction "22_22") (pintype "passive"))
      (node (ref "RA8") (pin "1") (pinfunction "1_1") (pintype "passive"))
    )
    (net (code "83") (name "Net-(J2-Pad24)") (class "Default")
      (node (ref "J2") (pin "24") (pinfunction "24_24") (pintype "passive"))
      (node (ref "RA8") (pin "2") (pinfunction "2_2") (pintype "passive"))
    )
    (net (code "84") (name "Net-(J2-Pad28)") (class "Default")
      (node (ref "J2") (pin "28") (pinfunction "28_28") (pintype "passive"))
      (node (ref "RA8") (pin "3") (pinfunction "3_3") (pintype "passive"))
    )
    (net (code "85") (name "Net-(J2-Pad30)") (class "Default")
      (node (ref "J2") (pin "30") (pinfunction "30_30") (pintype "passive"))
      (node (ref "RA8") (pin "4") (pinfunction "4_4") (pintype "passive"))
    )
    (net (code "86") (name "Net-(J2-Pad34)") (class "Default")
      (node (ref "J2") (pin "34") (pinfunction "34_34") (pintype "passive"))
      (node (ref "RA7") (pin "1") (pinfunction "1_1") (pintype "passive"))
    )
    (net (code "87") (name "Net-(J2-Pad36)") (class "Default")
      (node (ref "J2") (pin "36") (pinfunction "36_36") (pintype "passive"))
      (node (ref "RA7") (pin "2") (pinfunction "2_2") (pintype "passive"))
    )
    (net (code "88") (name "Net-(J2-Pad40)") (class "Default")
      (node (ref "J2") (pin "40") (pinfunction "40_40") (pintype "passive"))
      (node (ref "RA7") (pin "3") (pinfunction "3_3") (pintype "passive"))
    )
    (net (code "89") (name "Net-(J2-Pad42)") (class "Default")
      (node (ref "J2") (pin "42") (pinfunction "42_42") (pintype "passive"))
      (node (ref "RA7") (pin "4") (pinfunction "4_4") (pintype "passive"))
    )
    (net (code "90") (name "Net-(J2-Pad46)") (class "Default")
      (node (ref "J2") (pin "46") (pinfunction "46_46") (pintype "passive"))
      (node (ref "RA6") (pin "1") (pinfunction "1_1") (pintype "passive"))
    )
    (net (code "91") (name "Net-(J2-Pad48)") (class "Default")
      (node (ref "J2") (pin "48") (pinfunction "48_48") (pintype "passive"))
      (node (ref "RA6") (pin "2") (pinfunction "2_2") (pintype "passive"))
    )
    (net (code "92") (name "Net-(J2-Pad52)") (class "Default")
      (node (ref "J2") (pin "52") (pinfunction "52_52") (pintype "passive"))
      (node (ref "RA6") (pin "3") (pinfunction "3_3") (pintype "passive"))
    )
    (net (code "93") (name "Net-(J2-Pad54)") (class "Default")
      (node (ref "J2") (pin "54") (pinfunction "54_54") (pintype "passive"))
      (node (ref "RA6") (pin "4") (pinfunction "4_4") (pintype "passive"))
    )
    (net (code "94") (name "Net-(J2-Pad56)") (class "Default")
      (node (ref "J2") (pin "56") (pinfunction "56_56") (pintype "passive"))
      (node (ref "RA5") (pin "1") (pinfunction "1_1") (pintype "passive"))
    )
    (net (code "95") (name "Net-(J2-Pad57)") (class "Default")
      (node (ref "J2") (pin "57") (pinfunction "57_57") (pintype "passive"))
      (node (ref "R14") (pin "1") (pinfunction "1_1") (pintype "passive"))
    )
    (net (code "96") (name "Net-(J2-Pad58)") (class "Default")
      (node (ref "J2") (pin "58") (pinfunction "58_58") (pintype "passive"))
      (node (ref "RA5") (pin "2") (pinfunction "2_2") (pintype "passive"))
    )
    (net (code "97") (name "Net-(J2-Pad59)") (class "Default")
      (node (ref "J2") (pin "59") (pinfunction "59_59") (pintype "passive"))
      (node (ref "R12") (pin "1") (pinfunction "1_1") (pintype "passive"))
    )
    (net (code "98") (name "Net-(J2-Pad60)") (class "Default")
      (node (ref "J2") (pin "60") (pinfunction "60_60") (pintype "passive"))
      (node (ref "RA5") (pin "3") (pinfunction "3_3") (pintype "passive"))
    )
    (net (code "99") (name "Net-(R58-Pad2)") (class "Default")
      (node (ref "R58") (pin "2") (pinfunction "2_2") (pintype "passive"))
      (node (ref "RA9") (pin "5") (pinfunction "5_5") (pintype "passive"))
    )
    (net (code "100") (name "Net-(U19-D0)") (class "Default")
      (node (ref "R92") (pin "1") (pinfunction "1_1") (pintype "passive"))
      (node (ref "U19") (pin "2") (pinfunction "D0_2") (pintype "input"))
    )
    (net (code "101") (name "Net-(U19-D1)") (class "Default")
      (node (ref "R20") (pin "2") (pinfunction "2_2") (pintype "passive"))
      (node (ref "R29") (pin "2") (pinfunction "2_2") (pintype "passive"))
      (node (ref "U19") (pin "3") (pinfunction "D1_3") (pintype "input"))
    )
    (net (code "102") (name "Net-(U19-ILIM)") (class "Default")
      (node (ref "R24") (pin "2") (pinfunction "2_2") (pintype "passive"))
      (node (ref "U19") (pin "4") (pinfunction "ILIM_4") (pintype "input"))
    )
    (net (code "103") (name "Net-(U19-STAT)") (class "Default")
      (node (ref "R27") (pin "2") (pinfunction "2_2") (pintype "passive"))
      (node (ref "TP10") (pin "1") (pintype "passive"))
      (node (ref "U19") (pin "1") (pinfunction "STAT_1") (pintype "tri_state"))
    )
    (net (code "104") (name "PMICOUT_3V3") (class "Default")
      (node (ref "FL22") (pin "1") (pinfunction "1_1") (pintype "passive"))
    )
    (net (code "105") (name "VCC_BA_3V3") (class "Default")
      (node (ref "FL22") (pin "2") (pinfunction "2_2") (pintype "passive"))
      (node (ref "TP13") (pin "1") (pintype "passive"))
    )
    (net (code "106") (name "unconnected-(J2-Pad1)") (class "Default")
      (node (ref "J2") (pin "1") (pinfunction "1_1") (pintype "passive+no_connect"))
    )
    (net (code "107") (name "unconnected-(J2-Pad3)") (class "Default")
      (node (ref "J2") (pin "3") (pinfunction "3_3") (pintype "passive+no_connect"))
    )
    (net (code "108") (name "unconnected-(J2-Pad4)") (class "Default")
      (node (ref "J2") (pin "4") (pinfunction "4_4") (pintype "passive+no_connect"))
    )
    (net (code "109") (name "unconnected-(J2-Pad5)") (class "Default")
      (node (ref "J2") (pin "5") (pinfunction "5_5") (pintype "passive+no_connect"))
    )
    (net (code "110") (name "unconnected-(J2-Pad6)") (class "Default")
      (node (ref "J2") (pin "6") (pinfunction "6_6") (pintype "passive+no_connect"))
    )
    (net (code "111") (name "unconnected-(J2-Pad7)") (class "Default")
      (node (ref "J2") (pin "7") (pinfunction "7_7") (pintype "passive+no_connect"))
    )
    (net (code "112") (name "unconnected-(J2-Pad9)") (class "Default")
      (node (ref "J2") (pin "9") (pinfunction "9_9") (pintype "passive+no_connect"))
    )
    (net (code "113") (name "unconnected-(RA2-Pad1)") (class "Default")
      (node (ref "RA2") (pin "1") (pinfunction "1_1") (pintype "passive+no_connect"))
    )
    (net (code "114") (name "unconnected-(RA2-Pad8)") (class "Default")
      (node (ref "RA2") (pin "8") (pinfunction "8_8") (pintype "passive+no_connect"))
    )
    (net (code "115") (name "unconnected-(RA5-Pad4)") (class "Default")
      (node (ref "RA5") (pin "4") (pinfunction "4_4") (pintype "passive+no_connect"))
    )
    (net (code "116") (name "unconnected-(RA5-Pad5)") (class "Default")
      (node (ref "RA5") (pin "5") (pinfunction "5_5") (pintype "passive+no_connect"))
    )
  )
)
